# MB_ddr.net
KiCad netlist of a schematic drawn in Altium Designer
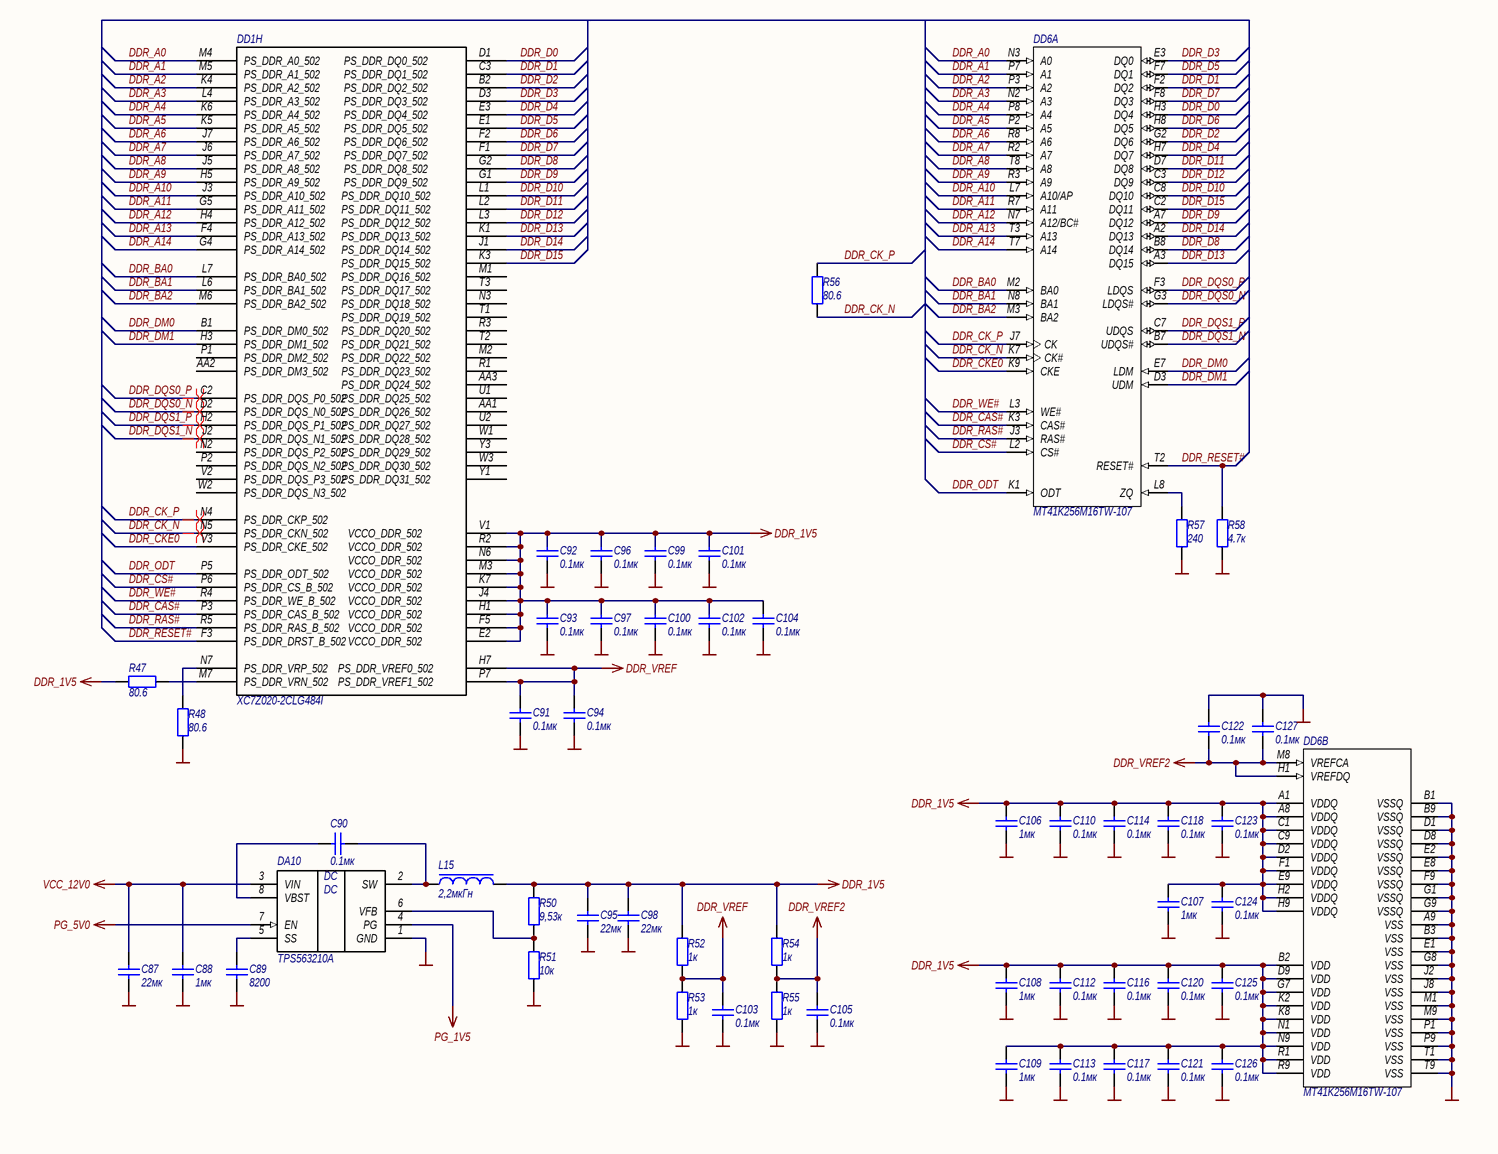
[diagram p0: MB_ddr.SchDoc]

(export (version "E")
  (design (tool "Eeschema 10.0.6"))
  (components
    (comp (ref "C87")
      (value "22мк")
      (footprint "CAPC2012X12L")
      (description "Кер. ЧИП-конденсатор")
      (fields (field (name "MANUFACTURER") "TDK") (field (name "TOLERANCE") "±10%"))
      (libsource (lib "nels_caps") (part "Кер.ЧИП конд. 0805 22мкФ X5R 10% 16В"))
    )
    (comp (ref "C88")
      (value "1мк")
      (footprint "CAPC1005X06N")
      (description "Кер. ЧИП-конденсатор")
      (fields (field (name "TOLERANCE") "±10%"))
      (libsource (lib "nels_caps") (part "Кер.ЧИП конд. 0402 1мкФ X5R 10%, 10В"))
    )
    (comp (ref "C89")
      (value "8200")
      (footprint "CAPC1005X06N")
      (description "Кер. ЧИП-конденсатор")
      (fields (field (name "TOLERANCE") "±20%"))
      (libsource (lib "nels_caps") (part "Кер.ЧИП конд. 0402 8200пФ X7R 10%, 50В"))
    )
    (comp (ref "C90")
      (value "0.1мк")
      (footprint "CAPC1005X06N")
      (description "Кер. ЧИП-конденсатор")
      (fields (field (name "TOLERANCE") "±10%"))
      (libsource (lib "nels") (part "Кер.ЧИП конд. 0402 0.1мкФ X7R 10%, 16В"))
    )
    (comp (ref "C91")
      (value "0.1мк")
      (footprint "CAPC1005X06N")
      (description "Кер. ЧИП-конденсатор")
      (fields (field (name "TOLERANCE") "±10%"))
      (libsource (lib "nels") (part "Кер.ЧИП конд. 0402 0.1мкФ X7R 10%, 16В"))
    )
    (comp (ref "C92")
      (value "0.1мк")
      (footprint "CAPC1005X06N")
      (description "Кер. ЧИП-конденсатор")
      (fields (field (name "TOLERANCE") "±10%"))
      (libsource (lib "nels") (part "Кер.ЧИП конд. 0402 0.1мкФ X7R 10%, 16В"))
    )
    (comp (ref "C93")
      (value "0.1мк")
      (footprint "CAPC1005X06N")
      (description "Кер. ЧИП-конденсатор")
      (fields (field (name "TOLERANCE") "±10%"))
      (libsource (lib "nels") (part "Кер.ЧИП конд. 0402 0.1мкФ X7R 10%, 16В"))
    )
    (comp (ref "C94")
      (value "0.1мк")
      (footprint "CAPC1005X06N")
      (description "Кер. ЧИП-конденсатор")
      (fields (field (name "TOLERANCE") "±10%"))
      (libsource (lib "nels") (part "Кер.ЧИП конд. 0402 0.1мкФ X7R 10%, 16В"))
    )
    (comp (ref "C95")
      (value "22мк")
      (footprint "CAPC2012X12L")
      (description "Кер. ЧИП-конденсатор")
      (fields (field (name "MANUFACTURER") "TDK") (field (name "TOLERANCE") "±10%"))
      (libsource (lib "nels_caps") (part "Кер.ЧИП конд. 0805 22мкФ X5R 10% 16В"))
    )
    (comp (ref "C96")
      (value "0.1мк")
      (footprint "CAPC1005X06N")
      (description "Кер. ЧИП-конденсатор")
      (fields (field (name "TOLERANCE") "±10%"))
      (libsource (lib "nels") (part "Кер.ЧИП конд. 0402 0.1мкФ X7R 10%, 16В"))
    )
    (comp (ref "C97")
      (value "0.1мк")
      (footprint "CAPC1005X06N")
      (description "Кер. ЧИП-конденсатор")
      (fields (field (name "TOLERANCE") "±10%"))
      (libsource (lib "nels") (part "Кер.ЧИП конд. 0402 0.1мкФ X7R 10%, 16В"))
    )
    (comp (ref "C98")
      (value "22мк")
      (footprint "CAPC2012X12L")
      (description "Кер. ЧИП-конденсатор")
      (fields (field (name "MANUFACTURER") "TDK") (field (name "TOLERANCE") "±10%"))
      (libsource (lib "nels_caps") (part "Кер.ЧИП конд. 0805 22мкФ X5R 10% 16В"))
    )
    (comp (ref "C99")
      (value "0.1мк")
      (footprint "CAPC1005X06N")
      (description "Кер. ЧИП-конденсатор")
      (fields (field (name "TOLERANCE") "±10%"))
      (libsource (lib "nels") (part "Кер.ЧИП конд. 0402 0.1мкФ X7R 10%, 16В"))
    )
    (comp (ref "C100")
      (value "0.1мк")
      (footprint "CAPC1005X06N")
      (description "Кер. ЧИП-конденсатор")
      (fields (field (name "TOLERANCE") "±10%"))
      (libsource (lib "nels") (part "Кер.ЧИП конд. 0402 0.1мкФ X7R 10%, 16В"))
    )
    (comp (ref "C101")
      (value "0.1мк")
      (footprint "CAPC1005X06N")
      (description "Кер. ЧИП-конденсатор")
      (fields (field (name "TOLERANCE") "±10%"))
      (libsource (lib "nels") (part "Кер.ЧИП конд. 0402 0.1мкФ X7R 10%, 16В"))
    )
    (comp (ref "C102")
      (value "0.1мк")
      (footprint "CAPC1005X06N")
      (description "Кер. ЧИП-конденсатор")
      (fields (field (name "TOLERANCE") "±10%"))
      (libsource (lib "nels") (part "Кер.ЧИП конд. 0402 0.1мкФ X7R 10%, 16В"))
    )
    (comp (ref "C103")
      (value "0.1мк")
      (footprint "CAPC1005X06N")
      (description "Кер. ЧИП-конденсатор")
      (fields (field (name "TOLERANCE") "±10%"))
      (libsource (lib "nels") (part "Кер.ЧИП конд. 0402 0.1мкФ X7R 10%, 16В"))
    )
    (comp (ref "C104")
      (value "0.1мк")
      (footprint "CAPC1005X06N")
      (description "Кер. ЧИП-конденсатор")
      (fields (field (name "TOLERANCE") "±10%"))
      (libsource (lib "nels") (part "Кер.ЧИП конд. 0402 0.1мкФ X7R 10%, 16В"))
    )
    (comp (ref "C105")
      (value "0.1мк")
      (footprint "CAPC1005X06N")
      (description "Кер. ЧИП-конденсатор")
      (fields (field (name "TOLERANCE") "±10%"))
      (libsource (lib "nels") (part "Кер.ЧИП конд. 0402 0.1мкФ X7R 10%, 16В"))
    )
    (comp (ref "C106")
      (value "1мк")
      (footprint "CAPC1005X06N")
      (description "Кер. ЧИП-конденсатор")
      (fields (field (name "TOLERANCE") "±10%"))
      (libsource (lib "nels") (part "Кер.ЧИП конд. 0402 1мкФ X5R 10%, 10В"))
    )
    (comp (ref "C107")
      (value "1мк")
      (footprint "CAPC1005X06N")
      (description "Кер. ЧИП-конденсатор")
      (fields (field (name "TOLERANCE") "±10%"))
      (libsource (lib "nels") (part "Кер.ЧИП конд. 0402 1мкФ X5R 10%, 10В"))
    )
    (comp (ref "C108")
      (value "1мк")
      (footprint "CAPC1005X06N")
      (description "Кер. ЧИП-конденсатор")
      (fields (field (name "TOLERANCE") "±10%"))
      (libsource (lib "nels") (part "Кер.ЧИП конд. 0402 1мкФ X5R 10%, 10В"))
    )
    (comp (ref "C109")
      (value "1мк")
      (footprint "CAPC1005X06N")
      (description "Кер. ЧИП-конденсатор")
      (fields (field (name "TOLERANCE") "±10%"))
      (libsource (lib "nels") (part "Кер.ЧИП конд. 0402 1мкФ X5R 10%, 10В"))
    )
    (comp (ref "C110")
      (value "0.1мк")
      (footprint "CAPC1005X06N")
      (description "Кер. ЧИП-конденсатор")
      (fields (field (name "TOLERANCE") "±10%"))
      (libsource (lib "nels") (part "Кер.ЧИП конд. 0402 0.1мкФ X7R 10%, 16В"))
    )
    (comp (ref "C112")
      (value "0.1мк")
      (footprint "CAPC1005X06N")
      (description "Кер. ЧИП-конденсатор")
      (fields (field (name "TOLERANCE") "±10%"))
      (libsource (lib "nels") (part "Кер.ЧИП конд. 0402 0.1мкФ X7R 10%, 16В"))
    )
    (comp (ref "C113")
      (value "0.1мк")
      (footprint "CAPC1005X06N")
      (description "Кер. ЧИП-конденсатор")
      (fields (field (name "TOLERANCE") "±10%"))
      (libsource (lib "nels") (part "Кер.ЧИП конд. 0402 0.1мкФ X7R 10%, 16В"))
    )
    (comp (ref "C114")
      (value "0.1мк")
      (footprint "CAPC1005X06N")
      (description "Кер. ЧИП-конденсатор")
      (fields (field (name "TOLERANCE") "±10%"))
      (libsource (lib "nels") (part "Кер.ЧИП конд. 0402 0.1мкФ X7R 10%, 16В"))
    )
    (comp (ref "C116")
      (value "0.1мк")
      (footprint "CAPC1005X06N")
      (description "Кер. ЧИП-конденсатор")
      (fields (field (name "TOLERANCE") "±10%"))
      (libsource (lib "nels") (part "Кер.ЧИП конд. 0402 0.1мкФ X7R 10%, 16В"))
    )
    (comp (ref "C117")
      (value "0.1мк")
      (footprint "CAPC1005X06N")
      (description "Кер. ЧИП-конденсатор")
      (fields (field (name "TOLERANCE") "±10%"))
      (libsource (lib "nels") (part "Кер.ЧИП конд. 0402 0.1мкФ X7R 10%, 16В"))
    )
    (comp (ref "C118")
      (value "0.1мк")
      (footprint "CAPC1005X06N")
      (description "Кер. ЧИП-конденсатор")
      (fields (field (name "TOLERANCE") "±10%"))
      (libsource (lib "nels") (part "Кер.ЧИП конд. 0402 0.1мкФ X7R 10%, 16В"))
    )
    (comp (ref "C120")
      (value "0.1мк")
      (footprint "CAPC1005X06N")
      (description "Кер. ЧИП-конденсатор")
      (fields (field (name "TOLERANCE") "±10%"))
      (libsource (lib "nels") (part "Кер.ЧИП конд. 0402 0.1мкФ X7R 10%, 16В"))
    )
    (comp (ref "C121")
      (value "0.1мк")
      (footprint "CAPC1005X06N")
      (description "Кер. ЧИП-конденсатор")
      (fields (field (name "TOLERANCE") "±10%"))
      (libsource (lib "nels") (part "Кер.ЧИП конд. 0402 0.1мкФ X7R 10%, 16В"))
    )
    (comp (ref "C122")
      (value "0.1мк")
      (footprint "CAPC1005X06N")
      (description "Кер. ЧИП-конденсатор")
      (fields (field (name "TOLERANCE") "±10%"))
      (libsource (lib "nels") (part "Кер.ЧИП конд. 0402 0.1мкФ X7R 10%, 16В"))
    )
    (comp (ref "C123")
      (value "0.1мк")
      (footprint "CAPC1005X06N")
      (description "Кер. ЧИП-конденсатор")
      (fields (field (name "TOLERANCE") "±10%"))
      (libsource (lib "nels") (part "Кер.ЧИП конд. 0402 0.1мкФ X7R 10%, 16В"))
    )
    (comp (ref "C124")
      (value "0.1мк")
      (footprint "CAPC1005X06N")
      (description "Кер. ЧИП-конденсатор")
      (fields (field (name "TOLERANCE") "±10%"))
      (libsource (lib "nels") (part "Кер.ЧИП конд. 0402 0.1мкФ X7R 10%, 16В"))
    )
    (comp (ref "C125")
      (value "0.1мк")
      (footprint "CAPC1005X06N")
      (description "Кер. ЧИП-конденсатор")
      (fields (field (name "TOLERANCE") "±10%"))
      (libsource (lib "nels") (part "Кер.ЧИП конд. 0402 0.1мкФ X7R 10%, 16В"))
    )
    (comp (ref "C126")
      (value "0.1мк")
      (footprint "CAPC1005X06N")
      (description "Кер. ЧИП-конденсатор")
      (fields (field (name "TOLERANCE") "±10%"))
      (libsource (lib "nels") (part "Кер.ЧИП конд. 0402 0.1мкФ X7R 10%, 16В"))
    )
    (comp (ref "C127")
      (value "0.1мк")
      (footprint "CAPC1005X06N")
      (description "Кер. ЧИП-конденсатор")
      (fields (field (name "TOLERANCE") "±10%"))
      (libsource (lib "nels") (part "Кер.ЧИП конд. 0402 0.1мкФ X7R 10%, 16В"))
    )
    (comp (ref "DA10")
      (value "TPS563210A")
      (footprint "TSOP65P280X110-8N")
      (description "TPS56x210A, 4.5-V to 17-V Input, 2-A, 3-A Synchrono")
      (fields (field (name "MANUFACTURER") "TI"))
      (libsource (lib "MB") (part "Микросхема TPS563210A"))
    )
    (comp (ref "DD1")
      (value "XC7Z020-2CLG484I")
      (footprint "BGA484C80P22X22_1900X1900X160")
      (description "Zynq®-7000 SoC Family")
      (fields (field (name "MANUFACTURER") "XILINX"))
      (libsource (lib "MB") (part "Микросхема XC7Z020-2CLG484I"))
    )
    (comp (ref "DD6")
      (value "MT41K256M16TW-107")
      (footprint "BGA96C80P9X16_800X1400X110")
      (description "4Gb, x16, 1.35V DDR3L")
      (fields (field (name "VOLTAGE") "1.35V") (field (name "MANUFACTURER") "Micron"))
      (libsource (lib "nels_chip") (part "Микросхема MT41K256M16TW-107"))
    )
    (comp (ref "L15")
      (value "2,2мкГн")
      (footprint "CSAB0420")
      (description "Molding Power Choke")
      (fields
        (field (name "MANUFACTURER") "Vishay")
        (field (name "MANUFACTURERPARTNUMBER") "IHLP1616ABER1R0M11")
      )
      (libsource (lib "nels_ind") (part "ЧИП индуктивность CSAB0420-2R2M"))
    )
    (comp (ref "R47")
      (value "80.6")
      (footprint "RESC1005X06N")
      (description "ЧИП-резистор")
      (fields (field (name "TOLERANCE") "±1%"))
      (libsource (lib "") (part "Чип резистор 0402 80,6 Ом, 1%_1_1"))
    )
    (comp (ref "R48")
      (value "80.6")
      (footprint "RESC1005X06N")
      (description "ЧИП-резистор")
      (fields (field (name "TOLERANCE") "±1%"))
      (libsource (lib "nels_res") (part "Чип резистор 0402 80,6 Ом, 1%_1"))
    )
    (comp (ref "R50")
      (value "9,53к")
      (footprint "RESC1005X06N")
      (description "ЧИП-резистор")
      (fields (field (name "TOLERANCE") "±1%"))
      (libsource (lib "nels_res") (part "Чип резистор 0402 9,53 кОм, 1%"))
    )
    (comp (ref "R51")
      (value "10к")
      (footprint "RESC1005X06N")
      (description "ЧИП-резистор")
      (fields (field (name "TOLERANCE") "±5%"))
      (libsource (lib "nels_res") (part "Чип резистор 0402 10 кОм, 1%"))
    )
    (comp (ref "R52")
      (value "1к")
      (footprint "RESC1005X06N")
      (description "ЧИП-резистор")
      (fields (field (name "TOLERANCE") "±5%"))
      (libsource (lib "nels_res") (part "Чип резистор 0402 1 кОм, 5%"))
    )
    (comp (ref "R53")
      (value "1к")
      (footprint "RESC1005X06N")
      (description "ЧИП-резистор")
      (fields (field (name "TOLERANCE") "±5%"))
      (libsource (lib "nels_res") (part "Чип резистор 0402 1 кОм, 5%"))
    )
    (comp (ref "R54")
      (value "1к")
      (footprint "RESC1005X06N")
      (description "ЧИП-резистор")
      (fields (field (name "TOLERANCE") "±5%"))
      (libsource (lib "nels_res") (part "Чип резистор 0402 1 кОм, 5%"))
    )
    (comp (ref "R55")
      (value "1к")
      (footprint "RESC1005X06N")
      (description "ЧИП-резистор")
      (fields (field (name "TOLERANCE") "±5%"))
      (libsource (lib "nels_res") (part "Чип резистор 0402 1 кОм, 5%"))
    )
    (comp (ref "R56")
      (value "80.6")
      (footprint "RESC1005X06N")
      (description "ЧИП-резистор")
      (fields (field (name "TOLERANCE") "±1%"))
      (libsource (lib "nels_res") (part "Чип резистор 0402 80,6 Ом, 1%_1"))
    )
    (comp (ref "R57")
      (value "240")
      (footprint "RESC1005X06N")
      (description "ЧИП-резистор")
      (fields (field (name "TOLERANCE") "±5%"))
      (libsource (lib "nels_res") (part "Чип резистор 0402 240 Ом, 5%"))
    )
    (comp (ref "R58")
      (value "4.7к")
      (footprint "RESC1005X06N")
      (description "ЧИП-резистор")
      (fields (field (name "TOLERANCE") "±5%"))
      (libsource (lib "nels_res") (part "Чип резистор 0402 4,7 кОм, 5%"))
    )
  )
  (nets
    (net (code "1") (name "/DDR_A0") (class "Default")
      (node (ref "DD1") (pin "M4") (pinfunction "PS_DDR_A0_502_M4") (pintype "passive"))
      (node (ref "DD6") (pin "N3") (pinfunction "A0_N3") (pintype "input"))
    )
    (net (code "2") (name "/DDR_A1") (class "Default")
      (node (ref "DD1") (pin "M5") (pinfunction "PS_DDR_A1_502_M5") (pintype "passive"))
      (node (ref "DD6") (pin "P7") (pinfunction "A1_P7") (pintype "input"))
    )
    (net (code "3") (name "/DDR_A2") (class "Default")
      (node (ref "DD1") (pin "K4") (pinfunction "PS_DDR_A2_502_K4") (pintype "passive"))
      (node (ref "DD6") (pin "P3") (pinfunction "A2_P3") (pintype "input"))
    )
    (net (code "4") (name "/DDR_A3") (class "Default")
      (node (ref "DD1") (pin "L4") (pinfunction "PS_DDR_A3_502_L4") (pintype "passive"))
      (node (ref "DD6") (pin "N2") (pinfunction "A3_N2") (pintype "input"))
    )
    (net (code "5") (name "/DDR_A4") (class "Default")
      (node (ref "DD1") (pin "K6") (pinfunction "PS_DDR_A4_502_K6") (pintype "passive"))
      (node (ref "DD6") (pin "P8") (pinfunction "A4_P8") (pintype "input"))
    )
    (net (code "6") (name "/DDR_A5") (class "Default")
      (node (ref "DD1") (pin "K5") (pinfunction "PS_DDR_A5_502_K5") (pintype "passive"))
      (node (ref "DD6") (pin "P2") (pinfunction "A5_P2") (pintype "input"))
    )
    (net (code "7") (name "/DDR_A6") (class "Default")
      (node (ref "DD1") (pin "J7") (pinfunction "PS_DDR_A6_502_J7") (pintype "passive"))
      (node (ref "DD6") (pin "R8") (pinfunction "A6_R8") (pintype "input"))
    )
    (net (code "8") (name "/DDR_A7") (class "Default")
      (node (ref "DD1") (pin "J6") (pinfunction "PS_DDR_A7_502_J6") (pintype "passive"))
      (node (ref "DD6") (pin "R2") (pinfunction "A7_R2") (pintype "input"))
    )
    (net (code "9") (name "/DDR_A8") (class "Default")
      (node (ref "DD1") (pin "J5") (pinfunction "PS_DDR_A8_502_J5") (pintype "passive"))
      (node (ref "DD6") (pin "T8") (pinfunction "A8_T8") (pintype "input"))
    )
    (net (code "10") (name "/DDR_A9") (class "Default")
      (node (ref "DD1") (pin "H5") (pinfunction "PS_DDR_A9_502_H5") (pintype "passive"))
      (node (ref "DD6") (pin "R3") (pinfunction "A9_R3") (pintype "input"))
    )
    (net (code "11") (name "/DDR_A10") (class "Default")
      (node (ref "DD1") (pin "J3") (pinfunction "PS_DDR_A10_502_J3") (pintype "passive"))
      (node (ref "DD6") (pin "L7") (pinfunction "A10/AP_L7") (pintype "input"))
    )
    (net (code "12") (name "/DDR_A11") (class "Default")
      (node (ref "DD1") (pin "G5") (pinfunction "PS_DDR_A11_502_G5") (pintype "passive"))
      (node (ref "DD6") (pin "R7") (pinfunction "A11_R7") (pintype "input"))
    )
    (net (code "13") (name "/DDR_A12") (class "Default")
      (node (ref "DD1") (pin "H4") (pinfunction "PS_DDR_A12_502_H4") (pintype "passive"))
      (node (ref "DD6") (pin "N7") (pinfunction "A12/BC#_N7") (pintype "input"))
    )
    (net (code "14") (name "/DDR_A13") (class "Default")
      (node (ref "DD1") (pin "F4") (pinfunction "PS_DDR_A13_502_F4") (pintype "passive"))
      (node (ref "DD6") (pin "T3") (pinfunction "A13_T3") (pintype "input"))
    )
    (net (code "15") (name "/DDR_A14") (class "Default")
      (node (ref "DD1") (pin "G4") (pinfunction "PS_DDR_A14_502_G4") (pintype "passive"))
      (node (ref "DD6") (pin "T7") (pinfunction "A14_T7") (pintype "input"))
    )
    (net (code "16") (name "/DDR_BA0") (class "Default")
      (node (ref "DD1") (pin "L7") (pinfunction "PS_DDR_BA0_502_L7") (pintype "passive"))
      (node (ref "DD6") (pin "M2") (pinfunction "BA0_M2") (pintype "input"))
    )
    (net (code "17") (name "/DDR_BA1") (class "Default")
      (node (ref "DD1") (pin "L6") (pinfunction "PS_DDR_BA1_502_L6") (pintype "passive"))
      (node (ref "DD6") (pin "N8") (pinfunction "BA1_N8") (pintype "input"))
    )
    (net (code "18") (name "/DDR_BA2") (class "Default")
      (node (ref "DD1") (pin "M6") (pinfunction "PS_DDR_BA2_502_M6") (pintype "passive"))
      (node (ref "DD6") (pin "M3") (pinfunction "BA2_M3") (pintype "input"))
    )
    (net (code "19") (name "/DDR_CAS#") (class "Default")
      (node (ref "DD1") (pin "P3") (pinfunction "PS_DDR_CAS_B_502_P3") (pintype "passive"))
      (node (ref "DD6") (pin "K3") (pinfunction "CAS#_K3") (pintype "input"))
    )
    (net (code "20") (name "/DDR_CKE0") (class "Default")
      (node (ref "DD1") (pin "V3") (pinfunction "PS_DDR_CKE_502_V3") (pintype "passive"))
      (node (ref "DD6") (pin "K9") (pinfunction "CKE_K9") (pintype "input"))
    )
    (net (code "21") (name "/DDR_CK_N") (class "Default")
      (node (ref "DD1") (pin "N5") (pinfunction "PS_DDR_CKN_502_N5") (pintype "passive"))
      (node (ref "DD6") (pin "K7") (pinfunction "CK#_K7") (pintype "input"))
      (node (ref "R56") (pin "2") (pinfunction "2_2") (pintype "passive"))
    )
    (net (code "22") (name "/DDR_CK_P") (class "Default")
      (node (ref "DD1") (pin "N4") (pinfunction "PS_DDR_CKP_502_N4") (pintype "passive"))
      (node (ref "DD6") (pin "J7") (pinfunction "CK_J7") (pintype "input"))
      (node (ref "R56") (pin "1") (pinfunction "1_1") (pintype "passive"))
    )
    (net (code "23") (name "/DDR_CS#") (class "Default")
      (node (ref "DD1") (pin "P6") (pinfunction "PS_DDR_CS_B_502_P6") (pintype "passive"))
      (node (ref "DD6") (pin "L2") (pinfunction "CS#_L2") (pintype "input"))
    )
    (net (code "24") (name "/DDR_D0") (class "Default")
      (node (ref "DD1") (pin "D1") (pinfunction "PS_DDR_DQ0_502_D1") (pintype "passive"))
      (node (ref "DD6") (pin "H3") (pinfunction "DQ4_H3") (pintype "bidirectional"))
    )
    (net (code "25") (name "/DDR_D1") (class "Default")
      (node (ref "DD1") (pin "C3") (pinfunction "PS_DDR_DQ1_502_C3") (pintype "passive"))
      (node (ref "DD6") (pin "F2") (pinfunction "DQ2_F2") (pintype "bidirectional"))
    )
    (net (code "26") (name "/DDR_D2") (class "Default")
      (node (ref "DD1") (pin "B2") (pinfunction "PS_DDR_DQ2_502_B2") (pintype "passive"))
      (node (ref "DD6") (pin "G2") (pinfunction "DQ6_G2") (pintype "bidirectional"))
    )
    (net (code "27") (name "/DDR_D3") (class "Default")
      (node (ref "DD1") (pin "D3") (pinfunction "PS_DDR_DQ3_502_D3") (pintype "passive"))
      (node (ref "DD6") (pin "E3") (pinfunction "DQ0_E3") (pintype "bidirectional"))
    )
    (net (code "28") (name "/DDR_D4") (class "Default")
      (node (ref "DD1") (pin "E3") (pinfunction "PS_DDR_DQ4_502_E3") (pintype "passive"))
      (node (ref "DD6") (pin "H7") (pinfunction "DQ7_H7") (pintype "bidirectional"))
    )
    (net (code "29") (name "/DDR_D5") (class "Default")
      (node (ref "DD1") (pin "E1") (pinfunction "PS_DDR_DQ5_502_E1") (pintype "passive"))
      (node (ref "DD6") (pin "F7") (pinfunction "DQ1_F7") (pintype "bidirectional"))
    )
    (net (code "30") (name "/DDR_D6") (class "Default")
      (node (ref "DD1") (pin "F2") (pinfunction "PS_DDR_DQ6_502_F2") (pintype "passive"))
      (node (ref "DD6") (pin "H8") (pinfunction "DQ5_H8") (pintype "bidirectional"))
    )
    (net (code "31") (name "/DDR_D7") (class "Default")
      (node (ref "DD1") (pin "F1") (pinfunction "PS_DDR_DQ7_502_F1") (pintype "passive"))
      (node (ref "DD6") (pin "F8") (pinfunction "DQ3_F8") (pintype "bidirectional"))
    )
    (net (code "32") (name "/DDR_D8") (class "Default")
      (node (ref "DD1") (pin "G2") (pinfunction "PS_DDR_DQ8_502_G2") (pintype "passive"))
      (node (ref "DD6") (pin "B8") (pinfunction "DQ14_B8") (pintype "bidirectional"))
    )
    (net (code "33") (name "/DDR_D9") (class "Default")
      (node (ref "DD1") (pin "G1") (pinfunction "PS_DDR_DQ9_502_G1") (pintype "passive"))
      (node (ref "DD6") (pin "A7") (pinfunction "DQ12_A7") (pintype "bidirectional"))
    )
    (net (code "34") (name "/DDR_D10") (class "Default")
      (node (ref "DD1") (pin "L1") (pinfunction "PS_DDR_DQ10_502_L1") (pintype "passive"))
      (node (ref "DD6") (pin "C8") (pinfunction "DQ10_C8") (pintype "bidirectional"))
    )
    (net (code "35") (name "/DDR_D11") (class "Default")
      (node (ref "DD1") (pin "L2") (pinfunction "PS_DDR_DQ11_502_L2") (pintype "passive"))
      (node (ref "DD6") (pin "D7") (pinfunction "DQ8_D7") (pintype "bidirectional"))
    )
    (net (code "36") (name "/DDR_D12") (class "Default")
      (node (ref "DD1") (pin "L3") (pinfunction "PS_DDR_DQ12_502_L3") (pintype "passive"))
      (node (ref "DD6") (pin "C3") (pinfunction "DQ9_C3") (pintype "bidirectional"))
    )
    (net (code "37") (name "/DDR_D13") (class "Default")
      (node (ref "DD1") (pin "K1") (pinfunction "PS_DDR_DQ13_502_K1") (pintype "passive"))
      (node (ref "DD6") (pin "A3") (pinfunction "DQ15_A3") (pintype "bidirectional"))
    )
    (net (code "38") (name "/DDR_D14") (class "Default")
      (node (ref "DD1") (pin "J1") (pinfunction "PS_DDR_DQ14_502_J1") (pintype "passive"))
      (node (ref "DD6") (pin "A2") (pinfunction "DQ13_A2") (pintype "bidirectional"))
    )
    (net (code "39") (name "/DDR_D15") (class "Default")
      (node (ref "DD1") (pin "K3") (pinfunction "PS_DDR_DQ15_502_K3") (pintype "passive"))
      (node (ref "DD6") (pin "C2") (pinfunction "DQ11_C2") (pintype "bidirectional"))
    )
    (net (code "40") (name "/DDR_DM0") (class "Default")
      (node (ref "DD1") (pin "B1") (pinfunction "PS_DDR_DM0_502_B1") (pintype "passive"))
      (node (ref "DD6") (pin "E7") (pinfunction "LDM_E7") (pintype "input"))
    )
    (net (code "41") (name "/DDR_DM~{1}") (class "Default")
      (node (ref "DD1") (pin "H3") (pinfunction "PS_DDR_DM1_502_H3") (pintype "passive"))
      (node (ref "DD6") (pin "D3") (pinfunction "UDM_D3") (pintype "input"))
    )
    (net (code "42") (name "/DDR_DQS0_N") (class "Default")
      (node (ref "DD1") (pin "D2") (pinfunction "PS_DDR_DQS_N0_502_D2") (pintype "passive"))
      (node (ref "DD6") (pin "G3") (pinfunction "LDQS#_G3") (pintype "bidirectional"))
    )
    (net (code "43") (name "/DDR_DQS0_P") (class "Default")
      (node (ref "DD1") (pin "C2") (pinfunction "PS_DDR_DQS_P0_502_C2") (pintype "passive"))
      (node (ref "DD6") (pin "F3") (pinfunction "LDQS_F3") (pintype "bidirectional"))
    )
    (net (code "44") (name "/DDR_DQS1_N") (class "Default")
      (node (ref "DD1") (pin "J2") (pinfunction "PS_DDR_DQS_N1_502_J2") (pintype "passive"))
      (node (ref "DD6") (pin "B7") (pinfunction "UDQS#_B7") (pintype "bidirectional"))
    )
    (net (code "45") (name "/DDR_DQS1_P") (class "Default")
      (node (ref "DD1") (pin "H2") (pinfunction "PS_DDR_DQS_P1_502_H2") (pintype "passive"))
      (node (ref "DD6") (pin "C7") (pinfunction "UDQS_C7") (pintype "bidirectional"))
    )
    (net (code "46") (name "/DDR_ODT") (class "Default")
      (node (ref "DD1") (pin "P5") (pinfunction "PS_DDR_ODT_502_P5") (pintype "passive"))
      (node (ref "DD6") (pin "K1") (pinfunction "ODT_K1") (pintype "input"))
    )
    (net (code "47") (name "/DDR_RAS#") (class "Default")
      (node (ref "DD1") (pin "R5") (pinfunction "PS_DDR_RAS_B_502_R5") (pintype "passive"))
      (node (ref "DD6") (pin "J3") (pinfunction "RAS#_J3") (pintype "input"))
    )
    (net (code "48") (name "/DDR_RESET#") (class "Default")
      (node (ref "DD1") (pin "F3") (pinfunction "PS_DDR_DRST_B_502_F3") (pintype "passive"))
      (node (ref "DD6") (pin "T2") (pinfunction "RESET#_T2") (pintype "input"))
      (node (ref "R58") (pin "1") (pinfunction "1_1") (pintype "passive"))
    )
    (net (code "49") (name "/DDR_WE#") (class "Default")
      (node (ref "DD1") (pin "R4") (pinfunction "PS_DDR_WE_B_502_R4") (pintype "passive"))
      (node (ref "DD6") (pin "L3") (pinfunction "WE#_L3") (pintype "input"))
    )
    (net (code "50") (name "DDR_1V5") (class "Default")
      (node (ref "C100") (pin "2") (pinfunction "2_2") (pintype "passive"))
      (node (ref "C101") (pin "2") (pinfunction "2_2") (pintype "passive"))
      (node (ref "C102") (pin "2") (pinfunction "2_2") (pintype "passive"))
      (node (ref "C104") (pin "2") (pinfunction "2_2") (pintype "passive"))
      (node (ref "C106") (pin "2") (pinfunction "2_2") (pintype "passive"))
      (node (ref "C107") (pin "2") (pinfunction "2_2") (pintype "passive"))
      (node (ref "C108") (pin "2") (pinfunction "2_2") (pintype "passive"))
      (node (ref "C109") (pin "2") (pinfunction "2_2") (pintype "passive"))
      (node (ref "C110") (pin "2") (pinfunction "2_2") (pintype "passive"))
      (node (ref "C112") (pin "2") (pinfunction "2_2") (pintype "passive"))
      (node (ref "C113") (pin "2") (pinfunction "2_2") (pintype "passive"))
      (node (ref "C114") (pin "2") (pinfunction "2_2") (pintype "passive"))
      (node (ref "C116") (pin "2") (pinfunction "2_2") (pintype "passive"))
      (node (ref "C117") (pin "2") (pinfunction "2_2") (pintype "passive"))
      (node (ref "C118") (pin "2") (pinfunction "2_2") (pintype "passive"))
      (node (ref "C120") (pin "2") (pinfunction "2_2") (pintype "passive"))
      (node (ref "C121") (pin "2") (pinfunction "2_2") (pintype "passive"))
      (node (ref "C123") (pin "2") (pinfunction "2_2") (pintype "passive"))
      (node (ref "C124") (pin "2") (pinfunction "2_2") (pintype "passive"))
      (node (ref "C125") (pin "2") (pinfunction "2_2") (pintype "passive"))
      (node (ref "C126") (pin "2") (pinfunction "2_2") (pintype "passive"))
      (node (ref "C92") (pin "2") (pinfunction "2_2") (pintype "passive"))
      (node (ref "C93") (pin "2") (pinfunction "2_2") (pintype "passive"))
      (node (ref "C95") (pin "2") (pinfunction "2_2") (pintype "passive"))
      (node (ref "C96") (pin "2") (pinfunction "2_2") (pintype "passive"))
      (node (ref "C97") (pin "2") (pinfunction "2_2") (pintype "passive"))
      (node (ref "C98") (pin "2") (pinfunction "2_2") (pintype "passive"))
      (node (ref "C99") (pin "2") (pinfunction "2_2") (pintype "passive"))
      (node (ref "DD1") (pin "E2") (pinfunction "VCCO_DDR_502_E2") (pintype "passive"))
      (node (ref "DD1") (pin "F5") (pinfunction "VCCO_DDR_502_F5") (pintype "passive"))
      (node (ref "DD1") (pin "H1") (pinfunction "VCCO_DDR_502_H1") (pintype "passive"))
      (node (ref "DD1") (pin "J4") (pinfunction "VCCO_DDR_502_J4") (pintype "passive"))
      (node (ref "DD1") (pin "K7") (pinfunction "VCCO_DDR_502_K7") (pintype "passive"))
      (node (ref "DD1") (pin "M3") (pinfunction "VCCO_DDR_502_M3") (pintype "passive"))
      (node (ref "DD1") (pin "N6") (pinfunction "VCCO_DDR_502_N6") (pintype "passive"))
      (node (ref "DD1") (pin "R2") (pinfunction "VCCO_DDR_502_R2") (pintype "passive"))
      (node (ref "DD1") (pin "V1") (pinfunction "VCCO_DDR_502_V1") (pintype "passive"))
      (node (ref "DD6") (pin "A1") (pinfunction "VDDQ_A1") (pintype "power_in"))
      (node (ref "DD6") (pin "A8") (pinfunction "VDDQ_A8") (pintype "power_in"))
      (node (ref "DD6") (pin "B2") (pinfunction "VDD_B2") (pintype "power_in"))
      (node (ref "DD6") (pin "C1") (pinfunction "VDDQ_C1") (pintype "power_in"))
      (node (ref "DD6") (pin "C9") (pinfunction "VDDQ_C9") (pintype "power_in"))
      (node (ref "DD6") (pin "D2") (pinfunction "VDDQ_D2") (pintype "power_in"))
      (node (ref "DD6") (pin "D9") (pinfunction "VDD_D9") (pintype "power_in"))
      (node (ref "DD6") (pin "E9") (pinfunction "VDDQ_E9") (pintype "power_in"))
      (node (ref "DD6") (pin "F1") (pinfunction "VDDQ_F1") (pintype "power_in"))
      (node (ref "DD6") (pin "G7") (pinfunction "VDD_G7") (pintype "power_in"))
      (node (ref "DD6") (pin "H2") (pinfunction "VDDQ_H2") (pintype "power_in"))
      (node (ref "DD6") (pin "H9") (pinfunction "VDDQ_H9") (pintype "power_in"))
      (node (ref "DD6") (pin "K2") (pinfunction "VDD_K2") (pintype "power_in"))
      (node (ref "DD6") (pin "K8") (pinfunction "VDD_K8") (pintype "power_in"))
      (node (ref "DD6") (pin "N1") (pinfunction "VDD_N1") (pintype "power_in"))
      (node (ref "DD6") (pin "N9") (pinfunction "VDD_N9") (pintype "power_in"))
      (node (ref "DD6") (pin "R1") (pinfunction "VDD_R1") (pintype "power_in"))
      (node (ref "DD6") (pin "R9") (pinfunction "VDD_R9") (pintype "power_in"))
      (node (ref "L15") (pin "2") (pinfunction "2_2") (pintype "passive"))
      (node (ref "R47") (pin "2") (pinfunction "2_2") (pintype "passive"))
      (node (ref "R50") (pin "2") (pinfunction "2_2") (pintype "passive"))
      (node (ref "R52") (pin "1") (pinfunction "1_1") (pintype "passive"))
      (node (ref "R54") (pin "1") (pinfunction "1_1") (pintype "passive"))
    )
    (net (code "51") (name "DDR_VREF") (class "Default")
      (node (ref "C103") (pin "2") (pinfunction "2_2") (pintype "passive"))
      (node (ref "C91") (pin "2") (pinfunction "2_2") (pintype "passive"))
      (node (ref "C94") (pin "2") (pinfunction "2_2") (pintype "passive"))
      (node (ref "DD1") (pin "H7") (pinfunction "PS_DDR_VREF0_502_H7") (pintype "passive"))
      (node (ref "DD1") (pin "P7") (pinfunction "PS_DDR_VREF1_502_P7") (pintype "passive"))
      (node (ref "R52") (pin "2") (pinfunction "2_2") (pintype "passive"))
      (node (ref "R53") (pin "1") (pinfunction "1_1") (pintype "passive"))
    )
    (net (code "52") (name "DDR_VREF2") (class "Default")
      (node (ref "C105") (pin "2") (pinfunction "2_2") (pintype "passive"))
      (node (ref "C122") (pin "1") (pinfunction "1_1") (pintype "passive"))
      (node (ref "C127") (pin "1") (pinfunction "1_1") (pintype "passive"))
      (node (ref "DD6") (pin "H1") (pinfunction "VREFDQ_H1") (pintype "input"))
      (node (ref "DD6") (pin "M8") (pinfunction "VREFCA_M8") (pintype "input"))
      (node (ref "R54") (pin "2") (pinfunction "2_2") (pintype "passive"))
      (node (ref "R55") (pin "1") (pinfunction "1_1") (pintype "passive"))
    )
    (net (code "53") (name "GND") (class "Default")
      (node (ref "C100") (pin "1") (pinfunction "1_1") (pintype "passive"))
      (node (ref "C101") (pin "1") (pinfunction "1_1") (pintype "passive"))
      (node (ref "C102") (pin "1") (pinfunction "1_1") (pintype "passive"))
      (node (ref "C103") (pin "1") (pinfunction "1_1") (pintype "passive"))
      (node (ref "C104") (pin "1") (pinfunction "1_1") (pintype "passive"))
      (node (ref "C105") (pin "1") (pinfunction "1_1") (pintype "passive"))
      (node (ref "C106") (pin "1") (pinfunction "1_1") (pintype "passive"))
      (node (ref "C107") (pin "1") (pinfunction "1_1") (pintype "passive"))
      (node (ref "C108") (pin "1") (pinfunction "1_1") (pintype "passive"))
      (node (ref "C109") (pin "1") (pinfunction "1_1") (pintype "passive"))
      (node (ref "C110") (pin "1") (pinfunction "1_1") (pintype "passive"))
      (node (ref "C112") (pin "1") (pinfunction "1_1") (pintype "passive"))
      (node (ref "C113") (pin "1") (pinfunction "1_1") (pintype "passive"))
      (node (ref "C114") (pin "1") (pinfunction "1_1") (pintype "passive"))
      (node (ref "C116") (pin "1") (pinfunction "1_1") (pintype "passive"))
      (node (ref "C117") (pin "1") (pinfunction "1_1") (pintype "passive"))
      (node (ref "C118") (pin "1") (pinfunction "1_1") (pintype "passive"))
      (node (ref "C120") (pin "1") (pinfunction "1_1") (pintype "passive"))
      (node (ref "C121") (pin "1") (pinfunction "1_1") (pintype "passive"))
      (node (ref "C122") (pin "2") (pinfunction "2_2") (pintype "passive"))
      (node (ref "C123") (pin "1") (pinfunction "1_1") (pintype "passive"))
      (node (ref "C124") (pin "1") (pinfunction "1_1") (pintype "passive"))
      (node (ref "C125") (pin "1") (pinfunction "1_1") (pintype "passive"))
      (node (ref "C126") (pin "1") (pinfunction "1_1") (pintype "passive"))
      (node (ref "C127") (pin "2") (pinfunction "2_2") (pintype "passive"))
      (node (ref "C87") (pin "1") (pinfunction "1_1") (pintype "passive"))
      (node (ref "C88") (pin "1") (pinfunction "1_1") (pintype "passive"))
      (node (ref "C89") (pin "1") (pinfunction "1_1") (pintype "passive"))
      (node (ref "C91") (pin "1") (pinfunction "1_1") (pintype "passive"))
      (node (ref "C92") (pin "1") (pinfunction "1_1") (pintype "passive"))
      (node (ref "C93") (pin "1") (pinfunction "1_1") (pintype "passive"))
      (node (ref "C94") (pin "1") (pinfunction "1_1") (pintype "passive"))
      (node (ref "C95") (pin "1") (pinfunction "1_1") (pintype "passive"))
      (node (ref "C96") (pin "1") (pinfunction "1_1") (pintype "passive"))
      (node (ref "C97") (pin "1") (pinfunction "1_1") (pintype "passive"))
      (node (ref "C98") (pin "1") (pinfunction "1_1") (pintype "passive"))
      (node (ref "C99") (pin "1") (pinfunction "1_1") (pintype "passive"))
      (node (ref "DA10") (pin "1") (pinfunction "GND_1") (pintype "passive"))
      (node (ref "DD6") (pin "A9") (pinfunction "VSS_A9") (pintype "power_in"))
      (node (ref "DD6") (pin "B1") (pinfunction "VSSQ_B1") (pintype "power_in"))
      (node (ref "DD6") (pin "B3") (pinfunction "VSS_B3") (pintype "power_in"))
      (node (ref "DD6") (pin "B9") (pinfunction "VSSQ_B9") (pintype "power_in"))
      (node (ref "DD6") (pin "D1") (pinfunction "VSSQ_D1") (pintype "power_in"))
      (node (ref "DD6") (pin "D8") (pinfunction "VSSQ_D8") (pintype "power_in"))
      (node (ref "DD6") (pin "E1") (pinfunction "VSS_E1") (pintype "power_in"))
      (node (ref "DD6") (pin "E2") (pinfunction "VSSQ_E2") (pintype "power_in"))
      (node (ref "DD6") (pin "E8") (pinfunction "VSSQ_E8") (pintype "power_in"))
      (node (ref "DD6") (pin "F9") (pinfunction "VSSQ_F9") (pintype "power_in"))
      (node (ref "DD6") (pin "G1") (pinfunction "VSSQ_G1") (pintype "power_in"))
      (node (ref "DD6") (pin "G8") (pinfunction "VSS_G8") (pintype "power_in"))
      (node (ref "DD6") (pin "G9") (pinfunction "VSSQ_G9") (pintype "power_in"))
      (node (ref "DD6") (pin "J2") (pinfunction "VSS_J2") (pintype "power_in"))
      (node (ref "DD6") (pin "J8") (pinfunction "VSS_J8") (pintype "power_in"))
      (node (ref "DD6") (pin "M1") (pinfunction "VSS_M1") (pintype "power_in"))
      (node (ref "DD6") (pin "M9") (pinfunction "VSS_M9") (pintype "power_in"))
      (node (ref "DD6") (pin "P1") (pinfunction "VSS_P1") (pintype "power_in"))
      (node (ref "DD6") (pin "P9") (pinfunction "VSS_P9") (pintype "power_in"))
      (node (ref "DD6") (pin "T1") (pinfunction "VSS_T1") (pintype "power_in"))
      (node (ref "DD6") (pin "T9") (pinfunction "VSS_T9") (pintype "power_in"))
      (node (ref "R48") (pin "2") (pinfunction "2_2") (pintype "passive"))
      (node (ref "R51") (pin "2") (pinfunction "2_2") (pintype "passive"))
      (node (ref "R53") (pin "2") (pinfunction "2_2") (pintype "passive"))
      (node (ref "R55") (pin "2") (pinfunction "2_2") (pintype "passive"))
      (node (ref "R57") (pin "2") (pinfunction "2_2") (pintype "passive"))
      (node (ref "R58") (pin "2") (pinfunction "2_2") (pintype "passive"))
    )
    (net (code "54") (name "Net-(DA10-SS)") (class "Default")
      (node (ref "C89") (pin "2") (pinfunction "2_2") (pintype "passive"))
      (node (ref "DA10") (pin "5") (pinfunction "SS_5") (pintype "passive"))
    )
    (net (code "55") (name "Net-(DA10-SW)") (class "Default")
      (node (ref "C90") (pin "1") (pinfunction "1_1") (pintype "passive"))
      (node (ref "DA10") (pin "2") (pinfunction "SW_2") (pintype "passive"))
      (node (ref "L15") (pin "1") (pinfunction "1_1") (pintype "passive"))
    )
    (net (code "56") (name "Net-(DA10-VBST)") (class "Default")
      (node (ref "C90") (pin "2") (pinfunction "2_2") (pintype "passive"))
      (node (ref "DA10") (pin "8") (pinfunction "VBST_8") (pintype "passive"))
    )
    (net (code "57") (name "Net-(DA10-VFB)") (class "Default")
      (node (ref "DA10") (pin "6") (pinfunction "VFB_6") (pintype "passive"))
      (node (ref "R50") (pin "1") (pinfunction "1_1") (pintype "passive"))
      (node (ref "R51") (pin "1") (pinfunction "1_1") (pintype "passive"))
    )
    (net (code "58") (name "Net-(DD1H-PS_DDR_VRN_502)") (class "Default")
      (node (ref "DD1") (pin "M7") (pinfunction "PS_DDR_VRN_502_M7") (pintype "passive"))
      (node (ref "R47") (pin "1") (pinfunction "1_1") (pintype "passive"))
    )
    (net (code "59") (name "Net-(DD1H-PS_DDR_VRP_502)") (class "Default")
      (node (ref "DD1") (pin "N7") (pinfunction "PS_DDR_VRP_502_N7") (pintype "passive"))
      (node (ref "R48") (pin "1") (pinfunction "1_1") (pintype "passive"))
    )
    (net (code "60") (name "Net-(DD6A-ZQ)") (class "Default")
      (node (ref "DD6") (pin "L8") (pinfunction "ZQ_L8") (pintype "input"))
      (node (ref "R57") (pin "1") (pinfunction "1_1") (pintype "passive"))
    )
    (net (code "61") (name "PG_1V5") (class "Default")
      (node (ref "DA10") (pin "4") (pinfunction "PG_4") (pintype "open_collector"))
    )
    (net (code "62") (name "PG_5V0") (class "Default")
      (node (ref "DA10") (pin "7") (pinfunction "EN_7") (pintype "input"))
    )
    (net (code "63") (name "VCC_12V0") (class "Default")
      (node (ref "C87") (pin "2") (pinfunction "2_2") (pintype "passive"))
      (node (ref "C88") (pin "2") (pinfunction "2_2") (pintype "passive"))
      (node (ref "DA10") (pin "3") (pinfunction "VIN_3") (pintype "passive"))
    )
    (net (code "64") (name "unconnected-(DD1H-PS_DDR_DM2_502-PadP1)") (class "Default")
      (node (ref "DD1") (pin "P1") (pinfunction "PS_DDR_DM2_502_P1") (pintype "passive"))
    )
    (net (code "65") (name "unconnected-(DD1H-PS_DDR_DM3_502-PadAA2)") (class "Default")
      (node (ref "DD1") (pin "AA2") (pinfunction "PS_DDR_DM3_502_AA2") (pintype "passive"))
    )
    (net (code "66") (name "unconnected-(DD1H-PS_DDR_DQ16_502-PadM1)") (class "Default")
      (node (ref "DD1") (pin "M1") (pinfunction "PS_DDR_DQ16_502_M1") (pintype "passive"))
    )
    (net (code "67") (name "unconnected-(DD1H-PS_DDR_DQ17_502-PadT3)") (class "Default")
      (node (ref "DD1") (pin "T3") (pinfunction "PS_DDR_DQ17_502_T3") (pintype "passive"))
    )
    (net (code "68") (name "unconnected-(DD1H-PS_DDR_DQ18_502-PadN3)") (class "Default")
      (node (ref "DD1") (pin "N3") (pinfunction "PS_DDR_DQ18_502_N3") (pintype "passive"))
    )
    (net (code "69") (name "unconnected-(DD1H-PS_DDR_DQ19_502-PadT1)") (class "Default")
      (node (ref "DD1") (pin "T1") (pinfunction "PS_DDR_DQ19_502_T1") (pintype "passive"))
    )
    (net (code "70") (name "unconnected-(DD1H-PS_DDR_DQ20_502-PadR3)") (class "Default")
      (node (ref "DD1") (pin "R3") (pinfunction "PS_DDR_DQ20_502_R3") (pintype "passive"))
    )
    (net (code "71") (name "unconnected-(DD1H-PS_DDR_DQ21_502-PadT2)") (class "Default")
      (node (ref "DD1") (pin "T2") (pinfunction "PS_DDR_DQ21_502_T2") (pintype "passive"))
    )
    (net (code "72") (name "unconnected-(DD1H-PS_DDR_DQ22_502-PadM2)") (class "Default")
      (node (ref "DD1") (pin "M2") (pinfunction "PS_DDR_DQ22_502_M2") (pintype "passive"))
    )
    (net (code "73") (name "unconnected-(DD1H-PS_DDR_DQ23_502-PadR1)") (class "Default")
      (node (ref "DD1") (pin "R1") (pinfunction "PS_DDR_DQ23_502_R1") (pintype "passive"))
    )
    (net (code "74") (name "unconnected-(DD1H-PS_DDR_DQ24_502-PadAA3)") (class "Default")
      (node (ref "DD1") (pin "AA3") (pinfunction "PS_DDR_DQ24_502_AA3") (pintype "passive"))
    )
    (net (code "75") (name "unconnected-(DD1H-PS_DDR_DQ25_502-PadU1)") (class "Default")
      (node (ref "DD1") (pin "U1") (pinfunction "PS_DDR_DQ25_502_U1") (pintype "passive"))
    )
    (net (code "76") (name "unconnected-(DD1H-PS_DDR_DQ26_502-PadAA1)") (class "Default")
      (node (ref "DD1") (pin "AA1") (pinfunction "PS_DDR_DQ26_502_AA1") (pintype "passive"))
    )
    (net (code "77") (name "unconnected-(DD1H-PS_DDR_DQ27_502-PadU2)") (class "Default")
      (node (ref "DD1") (pin "U2") (pinfunction "PS_DDR_DQ27_502_U2") (pintype "passive"))
    )
    (net (code "78") (name "unconnected-(DD1H-PS_DDR_DQ28_502-PadW1)") (class "Default")
      (node (ref "DD1") (pin "W1") (pinfunction "PS_DDR_DQ28_502_W1") (pintype "passive"))
    )
    (net (code "79") (name "unconnected-(DD1H-PS_DDR_DQ29_502-PadY3)") (class "Default")
      (node (ref "DD1") (pin "Y3") (pinfunction "PS_DDR_DQ29_502_Y3") (pintype "passive"))
    )
    (net (code "80") (name "unconnected-(DD1H-PS_DDR_DQ30_502-PadW3)") (class "Default")
      (node (ref "DD1") (pin "W3") (pinfunction "PS_DDR_DQ30_502_W3") (pintype "passive"))
    )
    (net (code "81") (name "unconnected-(DD1H-PS_DDR_DQ31_502-PadY1)") (class "Default")
      (node (ref "DD1") (pin "Y1") (pinfunction "PS_DDR_DQ31_502_Y1") (pintype "passive"))
    )
    (net (code "82") (name "unconnected-(DD1H-PS_DDR_DQS_N2_502-PadP2)") (class "Default")
      (node (ref "DD1") (pin "P2") (pinfunction "PS_DDR_DQS_N2_502_P2") (pintype "passive"))
    )
    (net (code "83") (name "unconnected-(DD1H-PS_DDR_DQS_N3_502-PadW2)") (class "Default")
      (node (ref "DD1") (pin "W2") (pinfunction "PS_DDR_DQS_N3_502_W2") (pintype "passive"))
    )
    (net (code "84") (name "unconnected-(DD1H-PS_DDR_DQS_P2_502-PadN2)") (class "Default")
      (node (ref "DD1") (pin "N2") (pinfunction "PS_DDR_DQS_P2_502_N2") (pintype "passive"))
    )
    (net (code "85") (name "unconnected-(DD1H-PS_DDR_DQS_P3_502-PadV2)") (class "Default")
      (node (ref "DD1") (pin "V2") (pinfunction "PS_DDR_DQS_P3_502_V2") (pintype "passive"))
    )
  )
)
